# clock-dist.net
KiCad netlist of a schematic drawn in Altium Designer
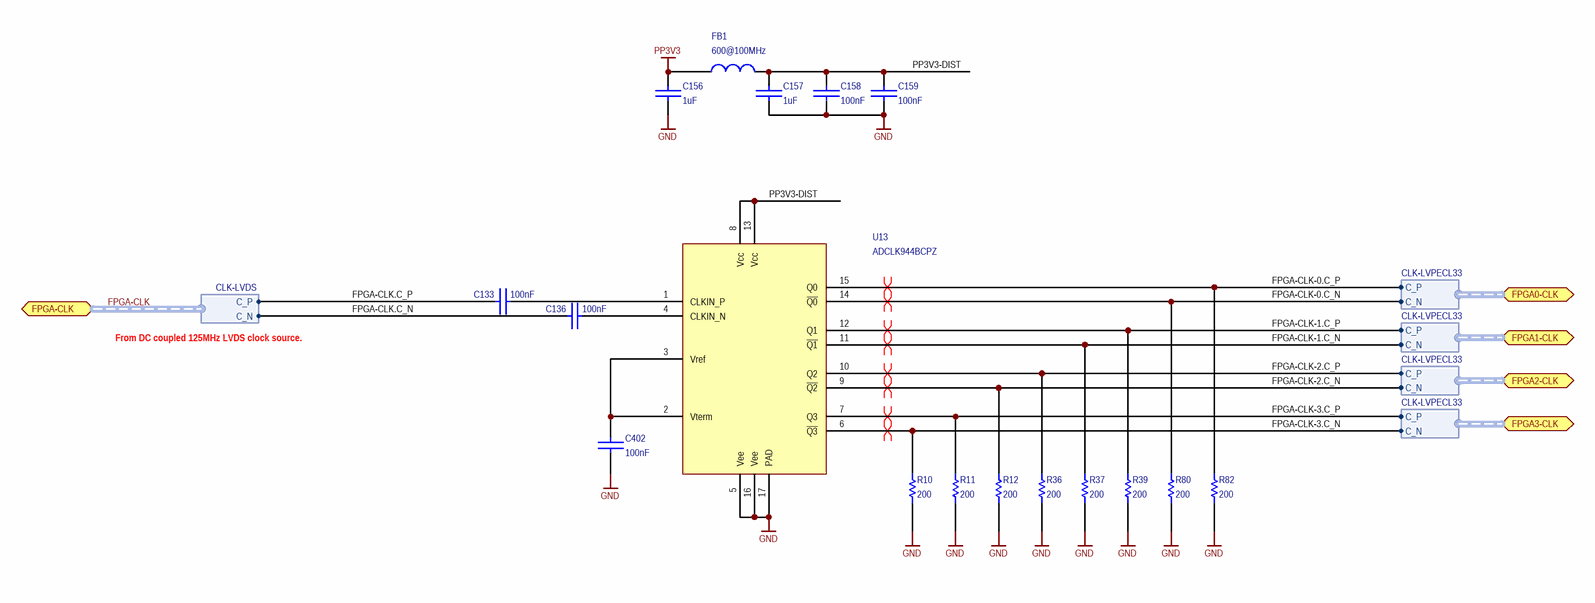
[diagram p0: clock-dist.SchDoc]

(export (version "E")
  (design (tool "Eeschema 10.0.6"))
  (components
    (comp (ref "C133")
      (value "100nF")
      (footprint "generic:0402")
      (description "Ceramic Capacitor SMD")
      (fields (field (name "MANUFACTURER") "Murata") (field (name "VOLTAGE") "16V"))
      (libsource (lib "*") (part "CAP"))
    )
    (comp (ref "C136")
      (value "100nF")
      (footprint "generic:0402")
      (description "Ceramic Capacitor SMD")
      (fields (field (name "MANUFACTURER") "Murata") (field (name "VOLTAGE") "16V"))
      (libsource (lib "*") (part "CAP"))
    )
    (comp (ref "C156")
      (value "1uF")
      (footprint "generic:0402")
      (description "Ceramic Capacitor SMD")
      (fields (field (name "MANUFACTURER") "Murata") (field (name "Comment") "GRM155R61A105KE15D"))
      (libsource (lib "*") (part "CAP"))
    )
    (comp (ref "C157")
      (value "1uF")
      (footprint "generic:0402")
      (description "Ceramic Capacitor SMD")
      (fields (field (name "MANUFACTURER") "Murata") (field (name "Comment") "GRM155R61A105KE15D"))
      (libsource (lib "*") (part "CAP"))
    )
    (comp (ref "C158")
      (value "100nF")
      (footprint "generic:0402")
      (description "Ceramic Capacitor SMD")
      (fields (field (name "MANUFACTURER") "Murata") (field (name "VOLTAGE") "16V"))
      (libsource (lib "*") (part "CAP"))
    )
    (comp (ref "C159")
      (value "100nF")
      (footprint "generic:0402")
      (description "Ceramic Capacitor SMD")
      (fields (field (name "MANUFACTURER") "Murata") (field (name "VOLTAGE") "16V"))
      (libsource (lib "*") (part "CAP"))
    )
    (comp (ref "C402")
      (value "100nF")
      (footprint "generic:0402")
      (description "Ceramic Capacitor SMD")
      (fields (field (name "MANUFACTURER") "Murata") (field (name "VOLTAGE") "16V"))
      (libsource (lib "*") (part "CAP"))
    )
    (comp (ref "FB1")
      (value "600@100MHz")
      (footprint "0805")
      (description "Ferrite Bead 600-Ohm @ 100MHz 0805")
      (fields (field (name "MANUFACTURER") "Vishay Dale") (field (name "Comment") "ILHB0805ER601V"))
      (libsource (lib "*") (part "INDUCTANCE1"))
    )
    (comp (ref "R10")
      (value "200")
      (footprint "generic:0402")
      (description "Resistor, SMD 0402")
      (fields (field (name "MANUFACTURER") "Panasonic") (field (name "Comment") "ERJ-2RKF2000X"))
      (libsource (lib "Graviton") (part "RES 0402"))
    )
    (comp (ref "R11")
      (value "200")
      (footprint "generic:0402")
      (description "Resistor, SMD 0402")
      (fields (field (name "MANUFACTURER") "Panasonic") (field (name "Comment") "ERJ-2RKF2000X"))
      (libsource (lib "Graviton") (part "RES 0402"))
    )
    (comp (ref "R12")
      (value "200")
      (footprint "generic:0402")
      (description "Resistor, SMD 0402")
      (fields (field (name "MANUFACTURER") "Panasonic") (field (name "Comment") "ERJ-2RKF2000X"))
      (libsource (lib "Graviton") (part "RES 0402"))
    )
    (comp (ref "R36")
      (value "200")
      (footprint "generic:0402")
      (description "Resistor, SMD 0402")
      (fields (field (name "MANUFACTURER") "Panasonic") (field (name "Comment") "ERJ-2RKF2000X"))
      (libsource (lib "Graviton") (part "RES 0402"))
    )
    (comp (ref "R37")
      (value "200")
      (footprint "generic:0402")
      (description "Resistor, SMD 0402")
      (fields (field (name "MANUFACTURER") "Panasonic") (field (name "Comment") "ERJ-2RKF2000X"))
      (libsource (lib "Graviton") (part "RES 0402"))
    )
    (comp (ref "R39")
      (value "200")
      (footprint "generic:0402")
      (description "Resistor, SMD 0402")
      (fields (field (name "MANUFACTURER") "Panasonic") (field (name "Comment") "ERJ-2RKF2000X"))
      (libsource (lib "Graviton") (part "RES 0402"))
    )
    (comp (ref "R80")
      (value "200")
      (footprint "generic:0402")
      (description "Resistor, SMD 0402")
      (fields (field (name "MANUFACTURER") "Panasonic") (field (name "Comment") "ERJ-2RKF2000X"))
      (libsource (lib "Graviton") (part "RES 0402"))
    )
    (comp (ref "R82")
      (value "200")
      (footprint "generic:0402")
      (description "Resistor, SMD 0402")
      (fields (field (name "MANUFACTURER") "Panasonic") (field (name "Comment") "ERJ-2RKF2000X"))
      (libsource (lib "Graviton") (part "RES 0402"))
    )
    (comp (ref "U13")
      (value "ADCLK944BCPZ")
      (footprint "WFQFN-16")
      (description "Ultra Low Jitter 1:4 Differential Clock Buffer")
      (fields (field (name "MANUFACTURER") "Analog Devices"))
      (libsource (lib "analog_devices") (part "ADCLK944"))
    )
  )
  (nets
    (net (code "3") (name "/FPGA-CLK-0.C_N") (class "Default")
      (node (ref "R80") (pin "1") (pinfunction "1_1") (pintype "passive"))
      (node (ref "U13") (pin "14") (pinfunction "~{Q0}_14") (pintype "passive"))
    )
    (net (code "4") (name "/FPGA-CLK-0.C_P") (class "Default")
      (node (ref "R82") (pin "1") (pinfunction "1_1") (pintype "passive"))
      (node (ref "U13") (pin "15") (pinfunction "Q0_15") (pintype "passive"))
    )
    (net (code "5") (name "/FPGA-CLK-1.C_N") (class "Default")
      (node (ref "R37") (pin "1") (pinfunction "1_1") (pintype "passive"))
      (node (ref "U13") (pin "11") (pinfunction "~{Q1}_11") (pintype "passive"))
    )
    (net (code "6") (name "/FPGA-CLK-1.C_P") (class "Default")
      (node (ref "R39") (pin "1") (pinfunction "1_1") (pintype "passive"))
      (node (ref "U13") (pin "12") (pinfunction "Q1_12") (pintype "passive"))
    )
    (net (code "7") (name "/FPGA-CLK-2.C_N") (class "Default")
      (node (ref "R12") (pin "1") (pinfunction "1_1") (pintype "passive"))
      (node (ref "U13") (pin "9") (pinfunction "~{Q2}_9") (pintype "passive"))
    )
    (net (code "8") (name "/FPGA-CLK-2.C_P") (class "Default")
      (node (ref "R36") (pin "1") (pinfunction "1_1") (pintype "passive"))
      (node (ref "U13") (pin "10") (pinfunction "Q2_10") (pintype "passive"))
    )
    (net (code "9") (name "/FPGA-CLK-3.C_N") (class "Default")
      (node (ref "R10") (pin "1") (pinfunction "1_1") (pintype "passive"))
      (node (ref "U13") (pin "6") (pinfunction "~{Q3}_6") (pintype "passive"))
    )
    (net (code "10") (name "/FPGA-CLK-3.C_P") (class "Default")
      (node (ref "R11") (pin "1") (pinfunction "1_1") (pintype "passive"))
      (node (ref "U13") (pin "7") (pinfunction "Q3_7") (pintype "passive"))
    )
    (net (code "11") (name "/FPGA-CLK.C_N") (class "Default")
      (node (ref "C136") (pin "2") (pinfunction "2_2") (pintype "passive"))
    )
    (net (code "12") (name "/FPGA-CLK.C_P") (class "Default")
      (node (ref "C133") (pin "2") (pinfunction "2_2") (pintype "passive"))
    )
    (net (code "14") (name "/PP3V3-DIST") (class "Default")
      (node (ref "C157") (pin "2") (pinfunction "2_2") (pintype "passive"))
      (node (ref "C158") (pin "2") (pinfunction "2_2") (pintype "passive"))
      (node (ref "C159") (pin "2") (pinfunction "2_2") (pintype "passive"))
      (node (ref "FB1") (pin "1") (pinfunction "1_1") (pintype "passive"))
      (node (ref "U13") (pin "13") (pinfunction "Vcc_13") (pintype "passive"))
      (node (ref "U13") (pin "8") (pinfunction "Vcc_8") (pintype "passive"))
    )
    (net (code "16") (name "GND") (class "Default")
      (node (ref "C156") (pin "1") (pinfunction "1_1") (pintype "passive"))
      (node (ref "C157") (pin "1") (pinfunction "1_1") (pintype "passive"))
      (node (ref "C158") (pin "1") (pinfunction "1_1") (pintype "passive"))
      (node (ref "C159") (pin "1") (pinfunction "1_1") (pintype "passive"))
      (node (ref "C402") (pin "1") (pinfunction "1_1") (pintype "passive"))
      (node (ref "R10") (pin "2") (pinfunction "2_2") (pintype "passive"))
      (node (ref "R11") (pin "2") (pinfunction "2_2") (pintype "passive"))
      (node (ref "R12") (pin "2") (pinfunction "2_2") (pintype "passive"))
      (node (ref "R36") (pin "2") (pinfunction "2_2") (pintype "passive"))
      (node (ref "R37") (pin "2") (pinfunction "2_2") (pintype "passive"))
      (node (ref "R39") (pin "2") (pinfunction "2_2") (pintype "passive"))
      (node (ref "R80") (pin "2") (pinfunction "2_2") (pintype "passive"))
      (node (ref "R82") (pin "2") (pinfunction "2_2") (pintype "passive"))
      (node (ref "U13") (pin "16") (pinfunction "Vee_16") (pintype "passive"))
      (node (ref "U13") (pin "17") (pinfunction "PAD_17") (pintype "passive"))
      (node (ref "U13") (pin "5") (pinfunction "Vee_5") (pintype "passive"))
    )
    (net (code "17") (name "Net-(U13-CLKIN_N)") (class "Default")
      (node (ref "C136") (pin "1") (pinfunction "1_1") (pintype "passive"))
      (node (ref "U13") (pin "4") (pinfunction "CLKIN_N_4") (pintype "passive"))
    )
    (net (code "18") (name "Net-(U13-CLKIN_P)") (class "Default")
      (node (ref "C133") (pin "1") (pinfunction "1_1") (pintype "passive"))
      (node (ref "U13") (pin "1") (pinfunction "CLKIN_P_1") (pintype "passive"))
    )
    (net (code "19") (name "Net-(U13-Vref)") (class "Default")
      (node (ref "C402") (pin "2") (pinfunction "2_2") (pintype "passive"))
      (node (ref "U13") (pin "2") (pinfunction "Vterm_2") (pintype "passive"))
      (node (ref "U13") (pin "3") (pinfunction "Vref_3") (pintype "passive"))
    )
    (net (code "20") (name "PP3V3") (class "Default")
      (node (ref "C156") (pin "2") (pinfunction "2_2") (pintype "passive"))
      (node (ref "FB1") (pin "2") (pinfunction "2_2") (pintype "passive"))
    )
  )
)
